# etapa2.net
KiCad netlist of a schematic drawn in Altium Designer
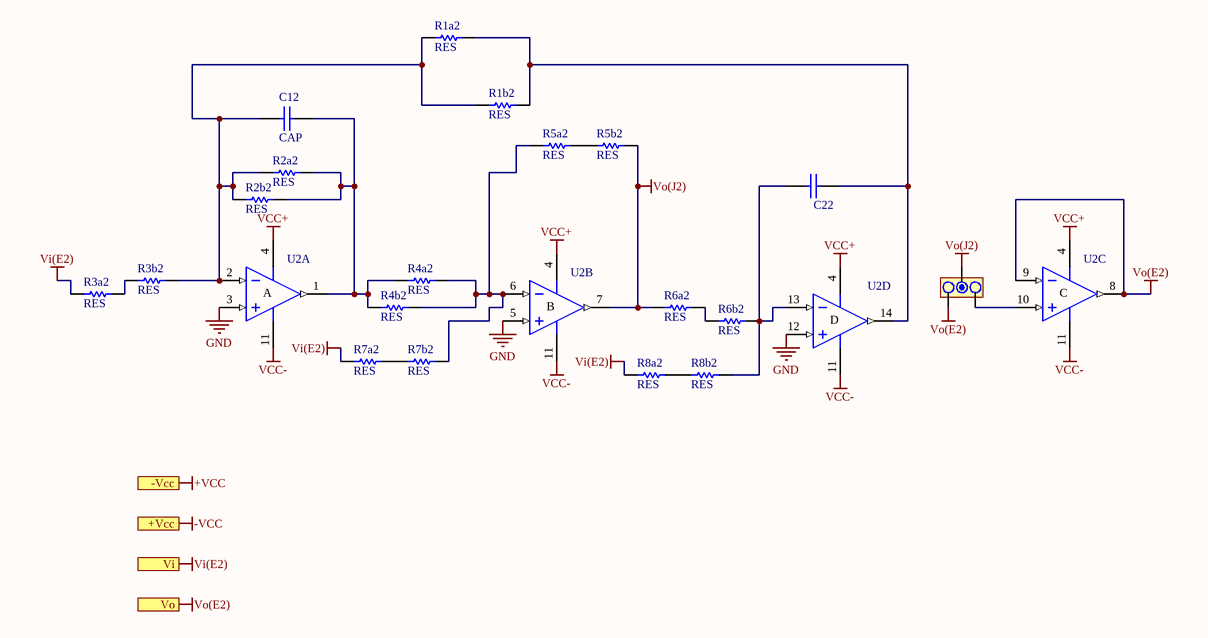
[diagram p0: etapa2.SchDoc]

(export (version "E")
  (design (tool "Eeschema 10.0.6"))
  (components
    (comp (ref "C12") (value "CAP") (footprint "CAP200") (libsource (lib "LIBEBAL") (part "CAP")))
    (comp (ref "C22") (value "CAP") (footprint "CAP200") (libsource (lib "LIBEBAL") (part "CAP")))
    (comp (ref "Jumper2") (value "JUMPER") (footprint "JUMPER3") (libsource (lib "LIBEBAL") (part "JUMPER3")))
    (comp (ref "R1a2") (value "RES") (footprint "0805") (libsource (lib "LIBEBAL") (part "RES")))
    (comp (ref "R1b2") (value "RES") (footprint "0805") (libsource (lib "LIBEBAL") (part "RES")))
    (comp (ref "R2a2") (value "RES") (footprint "0805") (libsource (lib "LIBEBAL") (part "RES")))
    (comp (ref "R2b2") (value "RES") (footprint "0805") (libsource (lib "LIBEBAL") (part "RES")))
    (comp (ref "R3a2") (value "RES") (footprint "0805") (libsource (lib "LIBEBAL") (part "RES")))
    (comp (ref "R3b2") (value "RES") (footprint "0805") (libsource (lib "LIBEBAL") (part "RES")))
    (comp (ref "R4a2") (value "RES") (footprint "0805") (libsource (lib "LIBEBAL") (part "RES")))
    (comp (ref "R4b2") (value "RES") (footprint "0805") (libsource (lib "LIBEBAL") (part "RES")))
    (comp (ref "R5a2") (value "RES") (footprint "0805") (libsource (lib "LIBEBAL") (part "RES")))
    (comp (ref "R5b2") (value "RES") (footprint "0805") (libsource (lib "LIBEBAL") (part "RES")))
    (comp (ref "R6a2") (value "RES") (footprint "0805") (libsource (lib "LIBEBAL") (part "RES")))
    (comp (ref "R6b2") (value "RES") (footprint "0805") (libsource (lib "LIBEBAL") (part "RES")))
    (comp (ref "R7a2") (value "RES") (footprint "0805") (libsource (lib "LIBEBAL") (part "RES")))
    (comp (ref "R7b2") (value "RES") (footprint "0805") (libsource (lib "LIBEBAL") (part "RES")))
    (comp (ref "R8a2") (value "RES") (footprint "0805") (libsource (lib "LIBEBAL") (part "RES")))
    (comp (ref "R8b2") (value "RES") (footprint "0805") (libsource (lib "LIBEBAL") (part "RES")))
    (comp (ref "U2")
      (value "TL084N")
      (footprint "N014")
      (description "JFET-Input Operational Amplifier")
      (fields (field (name "PUBLISHER") "Altium Limited"))
      (libsource (lib "TI Operational Amplifier") (part "TL084N"))
    )
  )
  (nets
    (net (code "3") (name "GND") (class "Default")
      (node (ref "U2") (pin "12") (pinfunction "IN+_12") (pintype "input"))
      (node (ref "U2") (pin "3") (pinfunction "IN+_3") (pintype "input"))
      (node (ref "U2") (pin "5") (pinfunction "IN+_5") (pintype "input"))
    )
    (net (code "4") (name "Net-(R3a2-Pad2)") (class "Default")
      (node (ref "R3a2") (pin "2") (pinfunction "2_2") (pintype "passive"))
      (node (ref "R3b2") (pin "1") (pinfunction "1_1") (pintype "passive"))
    )
    (net (code "5") (name "Net-(R5a2-Pad2)") (class "Default")
      (node (ref "R5a2") (pin "2") (pinfunction "2_2") (pintype "passive"))
      (node (ref "R5b2") (pin "1") (pinfunction "1_1") (pintype "passive"))
    )
    (net (code "6") (name "Net-(R6a2-Pad2)") (class "Default")
      (node (ref "R6a2") (pin "2") (pinfunction "2_2") (pintype "passive"))
      (node (ref "R6b2") (pin "1") (pinfunction "1_1") (pintype "passive"))
    )
    (net (code "7") (name "Net-(R7a2-Pad2)") (class "Default")
      (node (ref "R7a2") (pin "2") (pinfunction "2_2") (pintype "passive"))
      (node (ref "R7b2") (pin "1") (pinfunction "1_1") (pintype "passive"))
    )
    (net (code "8") (name "Net-(R8a2-Pad2)") (class "Default")
      (node (ref "R8a2") (pin "2") (pinfunction "2_2") (pintype "passive"))
      (node (ref "R8b2") (pin "1") (pinfunction "1_1") (pintype "passive"))
    )
    (net (code "9") (name "Net-(U2A-IN-)") (class "Default")
      (node (ref "C12") (pin "1") (pinfunction "1_1") (pintype "passive"))
      (node (ref "R1a2") (pin "1") (pinfunction "1_1") (pintype "passive"))
      (node (ref "R1b2") (pin "1") (pinfunction "1_1") (pintype "passive"))
      (node (ref "R2a2") (pin "1") (pinfunction "1_1") (pintype "passive"))
      (node (ref "R2b2") (pin "1") (pinfunction "1_1") (pintype "passive"))
      (node (ref "R3b2") (pin "2") (pinfunction "2_2") (pintype "passive"))
      (node (ref "U2") (pin "2") (pinfunction "IN-_2") (pintype "input"))
    )
    (net (code "10") (name "Net-(U2A-OUT)") (class "Default")
      (node (ref "C12") (pin "2") (pinfunction "2_2") (pintype "passive"))
      (node (ref "R2a2") (pin "2") (pinfunction "2_2") (pintype "passive"))
      (node (ref "R2b2") (pin "2") (pinfunction "2_2") (pintype "passive"))
      (node (ref "R4a2") (pin "1") (pinfunction "1_1") (pintype "passive"))
      (node (ref "R4b2") (pin "1") (pinfunction "1_1") (pintype "passive"))
      (node (ref "U2") (pin "1") (pinfunction "OUT_1") (pintype "output"))
    )
    (net (code "11") (name "Net-(U2B-IN-)") (class "Default")
      (node (ref "R4a2") (pin "2") (pinfunction "2_2") (pintype "passive"))
      (node (ref "R4b2") (pin "2") (pinfunction "2_2") (pintype "passive"))
      (node (ref "R5a2") (pin "1") (pinfunction "1_1") (pintype "passive"))
      (node (ref "R7b2") (pin "2") (pinfunction "2_2") (pintype "passive"))
      (node (ref "U2") (pin "6") (pinfunction "IN-_6") (pintype "input"))
    )
    (net (code "12") (name "Net-(U2C-IN+)") (class "Default")
      (node (ref "Jumper2") (pin "1") (pinfunction "1_1") (pintype "passive"))
      (node (ref "U2") (pin "10") (pinfunction "IN+_10") (pintype "input"))
    )
    (net (code "13") (name "Net-(U2D-IN-)") (class "Default")
      (node (ref "C22") (pin "1") (pinfunction "1_1") (pintype "passive"))
      (node (ref "R6b2") (pin "2") (pinfunction "2_2") (pintype "passive"))
      (node (ref "R8b2") (pin "2") (pinfunction "2_2") (pintype "passive"))
      (node (ref "U2") (pin "13") (pinfunction "IN-_13") (pintype "input"))
    )
    (net (code "14") (name "Net-(U2D-OUT)") (class "Default")
      (node (ref "C22") (pin "2") (pinfunction "2_2") (pintype "passive"))
      (node (ref "R1a2") (pin "2") (pinfunction "2_2") (pintype "passive"))
      (node (ref "R1b2") (pin "2") (pinfunction "2_2") (pintype "passive"))
      (node (ref "U2") (pin "14") (pinfunction "OUT_14") (pintype "output"))
    )
    (net (code "15") (name "VCC+") (class "Default")
      (node (ref "U2") (pin "4") (pinfunction "V+_4") (pintype "power_in"))
    )
    (net (code "16") (name "VCC-") (class "Default")
      (node (ref "U2") (pin "11") (pinfunction "V-_11") (pintype "power_in"))
    )
    (net (code "17") (name "Vi(E2)") (class "Default")
      (node (ref "R3a2") (pin "1") (pinfunction "1_1") (pintype "passive"))
      (node (ref "R7a2") (pin "1") (pinfunction "1_1") (pintype "passive"))
      (node (ref "R8a2") (pin "1") (pinfunction "1_1") (pintype "passive"))
    )
    (net (code "18") (name "Vo(E2)") (class "Default")
      (node (ref "Jumper2") (pin "3") (pinfunction "3_3") (pintype "passive"))
      (node (ref "U2") (pin "8") (pinfunction "OUT_8") (pintype "output"))
      (node (ref "U2") (pin "9") (pinfunction "IN-_9") (pintype "input"))
    )
    (net (code "19") (name "Vo(J2)") (class "Default")
      (node (ref "Jumper2") (pin "2") (pinfunction "2_2") (pintype "passive"))
      (node (ref "R5b2") (pin "2") (pinfunction "2_2") (pintype "passive"))
      (node (ref "R6a2") (pin "1") (pinfunction "1_1") (pintype "passive"))
      (node (ref "U2") (pin "7") (pinfunction "OUT_7") (pintype "output"))
    )
  )
)
